# com_board.net
KiCad netlist of a schematic drawn in EAGLE
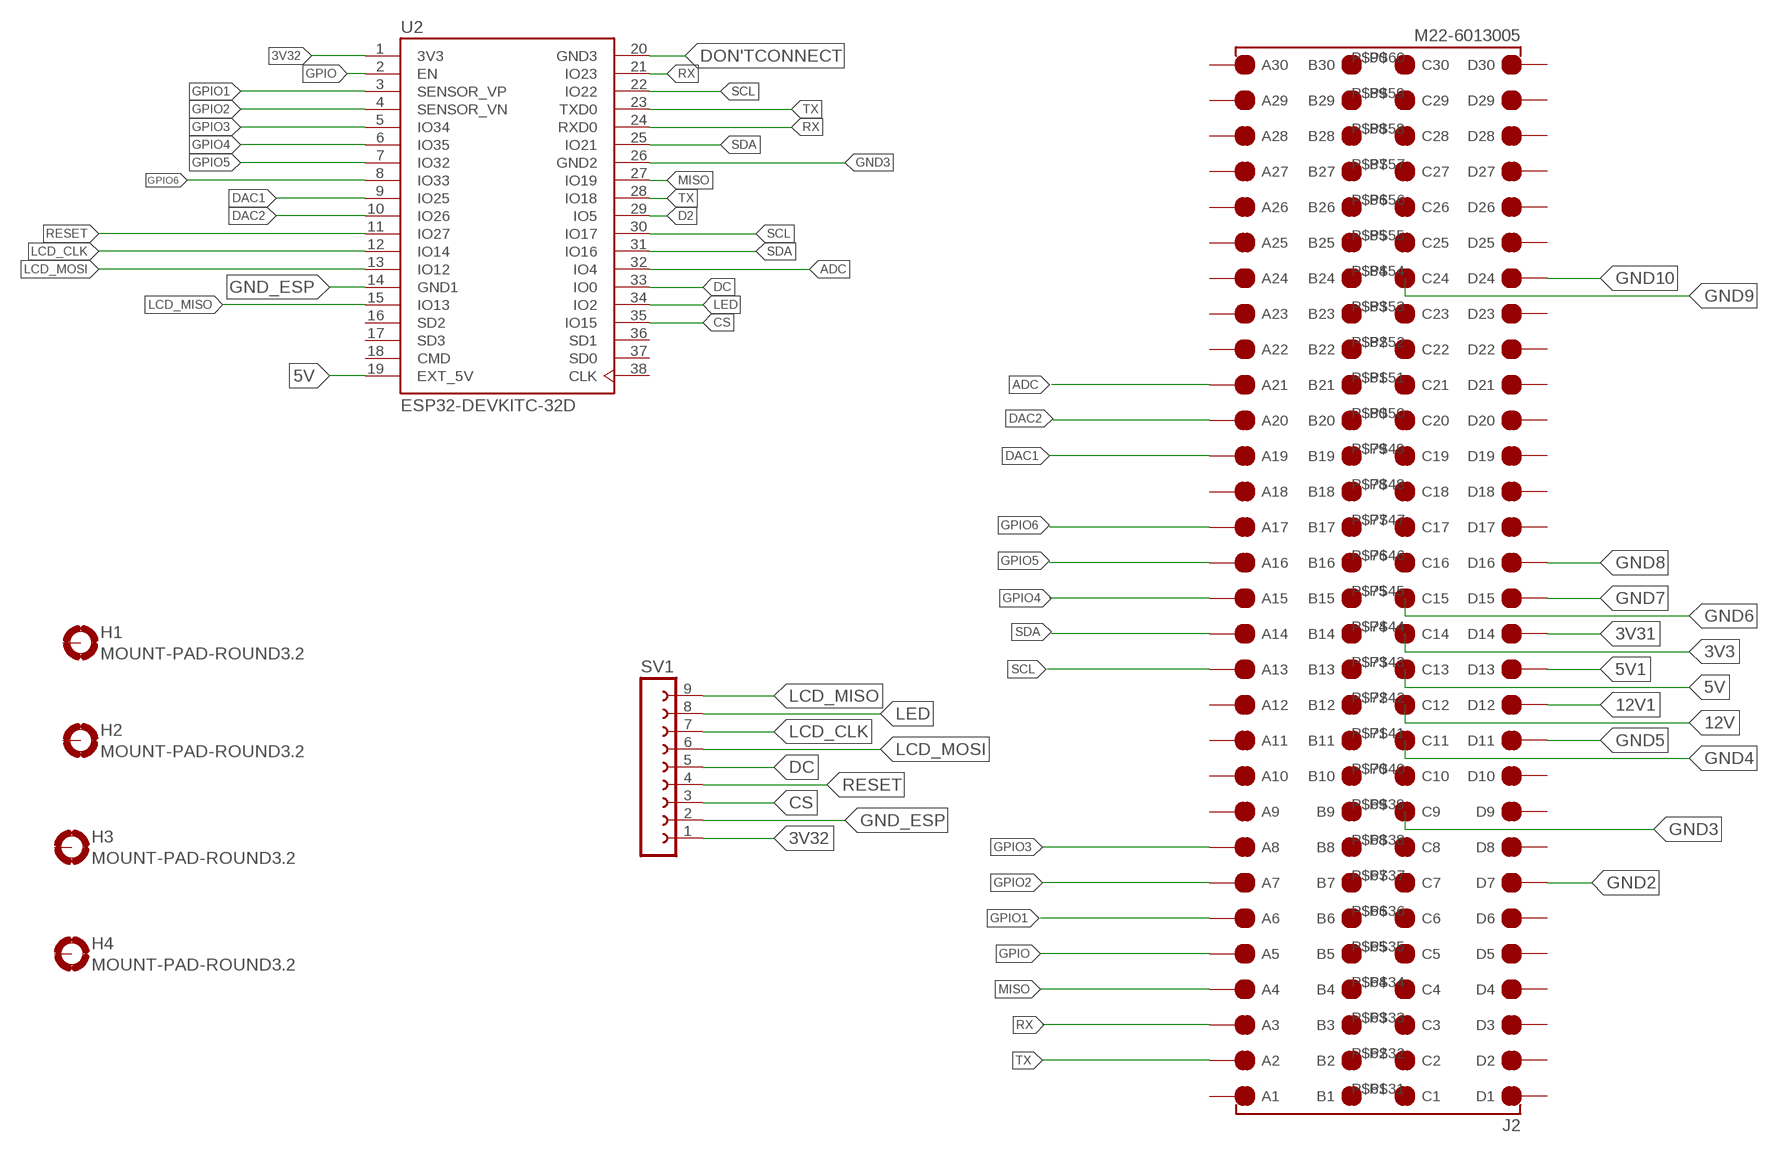
[diagram p0: schematic, sheet 1]

(export (version "E")
  (design (tool "Eeschema 10.0.6"))
  (components
    (comp (ref "H1")
      (value "MOUNT-PAD-ROUND3.2")
      (footprint "eagle-import:3,2-PAD")
      (libsource (lib "eagle-import") (part "MOUNT-PAD-ROUND3.2"))
    )
    (comp (ref "H2")
      (value "MOUNT-PAD-ROUND3.2")
      (footprint "eagle-import:3,2-PAD")
      (libsource (lib "eagle-import") (part "MOUNT-PAD-ROUND3.2"))
    )
    (comp (ref "H3")
      (value "MOUNT-PAD-ROUND3.2")
      (footprint "eagle-import:3,2-PAD")
      (libsource (lib "eagle-import") (part "MOUNT-PAD-ROUND3.2"))
    )
    (comp (ref "H4")
      (value "MOUNT-PAD-ROUND3.2")
      (footprint "eagle-import:3,2-PAD")
      (libsource (lib "eagle-import") (part "MOUNT-PAD-ROUND3.2"))
    )
    (comp (ref "J2")
      (value "M22-6013005")
      (footprint "eagle-import:RHDR120W55P200_4X30_6020X820X9")
      (libsource (lib "eagle-import") (part "M22-6013005"))
    )
    (comp (ref "SV1")
      (value "FE09-1")
      (footprint "eagle-import:FE09")
      (libsource (lib "eagle-import") (part "FE09-1"))
    )
    (comp (ref "U2")
      (value "ESP32-DEVKITC-32D")
      (footprint "eagle-import:MODULE_ESP32-DEVKITC-32D")
      (fields (field (name "MF") "Espressif Systems"))
      (libsource (lib "eagle-import") (part "ESP32-DEVKITC-32D"))
    )
  )
  (nets
    (net (code "1") (name "3V3") (class "Default")
      (node (ref "J2") (pin "P$44") (pinfunction "C14_P$44") (pintype "passive"))
    )
    (net (code "2") (name "3V31") (class "Default")
      (node (ref "J2") (pin "P$14") (pinfunction "D14_P$14") (pintype "passive"))
    )
    (net (code "3") (name "3V32") (class "Default")
      (node (ref "SV1") (pin "1") (pinfunction "1_1") (pintype "passive"))
      (node (ref "U2") (pin "1") (pinfunction "3V3_1") (pintype "power_in"))
    )
    (net (code "4") (name "5V") (class "Default")
      (node (ref "J2") (pin "P$43") (pinfunction "C13_P$43") (pintype "passive"))
      (node (ref "U2") (pin "19") (pinfunction "EXT_5V_19") (pintype "power_in"))
    )
    (net (code "5") (name "5V1") (class "Default")
      (node (ref "J2") (pin "P$13") (pinfunction "D13_P$13") (pintype "passive"))
    )
    (net (code "6") (name "12V") (class "Default")
      (node (ref "J2") (pin "P$42") (pinfunction "C12_P$42") (pintype "passive"))
    )
    (net (code "7") (name "12V1") (class "Default")
      (node (ref "J2") (pin "P$12") (pinfunction "D12_P$12") (pintype "passive"))
    )
    (net (code "8") (name "ADC") (class "Default")
      (node (ref "J2") (pin "P$111") (pinfunction "A21_P$111") (pintype "passive"))
      (node (ref "U2") (pin "32") (pinfunction "IO4_32") (pintype "bidirectional"))
    )
    (net (code "9") (name "CS") (class "Default")
      (node (ref "SV1") (pin "3") (pinfunction "3_3") (pintype "passive"))
      (node (ref "U2") (pin "35") (pinfunction "IO15_35") (pintype "bidirectional"))
    )
    (net (code "10") (name "D2") (class "Default")
      (node (ref "U2") (pin "29") (pinfunction "IO5_29") (pintype "bidirectional"))
    )
    (net (code "11") (name "DAC1") (class "Default")
      (node (ref "J2") (pin "P$109") (pinfunction "A19_P$109") (pintype "passive"))
      (node (ref "U2") (pin "9") (pinfunction "IO25_9") (pintype "bidirectional"))
    )
    (net (code "12") (name "DAC2") (class "Default")
      (node (ref "J2") (pin "P$110") (pinfunction "A20_P$110") (pintype "passive"))
      (node (ref "U2") (pin "10") (pinfunction "IO26_10") (pintype "bidirectional"))
    )
    (net (code "13") (name "DC") (class "Default")
      (node (ref "SV1") (pin "5") (pinfunction "5_5") (pintype "passive"))
      (node (ref "U2") (pin "33") (pinfunction "IO0_33") (pintype "bidirectional"))
    )
    (net (code "14") (name "DON'TCONNECT") (class "Default")
      (node (ref "U2") (pin "20") (pinfunction "GND3_20") (pintype "power_in"))
    )
    (net (code "15") (name "GND2") (class "Default")
      (node (ref "J2") (pin "P$7") (pinfunction "D7_P$7") (pintype "passive"))
    )
    (net (code "16") (name "GND3") (class "Default")
      (node (ref "J2") (pin "P$39") (pinfunction "C9_P$39") (pintype "passive"))
      (node (ref "U2") (pin "26") (pinfunction "GND2_26") (pintype "power_in"))
    )
    (net (code "17") (name "GND4") (class "Default")
      (node (ref "J2") (pin "P$41") (pinfunction "C11_P$41") (pintype "passive"))
    )
    (net (code "18") (name "GND5") (class "Default")
      (node (ref "J2") (pin "P$11") (pinfunction "D11_P$11") (pintype "passive"))
    )
    (net (code "19") (name "GND6") (class "Default")
      (node (ref "J2") (pin "P$45") (pinfunction "C15_P$45") (pintype "passive"))
    )
    (net (code "20") (name "GND7") (class "Default")
      (node (ref "J2") (pin "P$15") (pinfunction "D15_P$15") (pintype "passive"))
    )
    (net (code "21") (name "GND8") (class "Default")
      (node (ref "J2") (pin "P$16") (pinfunction "D16_P$16") (pintype "passive"))
    )
    (net (code "22") (name "GND9") (class "Default")
      (node (ref "J2") (pin "P$54") (pinfunction "C24_P$54") (pintype "passive"))
    )
    (net (code "23") (name "GND10") (class "Default")
      (node (ref "J2") (pin "P$24") (pinfunction "D24_P$24") (pintype "passive"))
    )
    (net (code "24") (name "GND_ESP") (class "Default")
      (node (ref "SV1") (pin "2") (pinfunction "2_2") (pintype "passive"))
      (node (ref "U2") (pin "14") (pinfunction "GND1_14") (pintype "power_in"))
    )
    (net (code "25") (name "GPIO") (class "Default")
      (node (ref "J2") (pin "P$95") (pinfunction "A5_P$95") (pintype "passive"))
      (node (ref "U2") (pin "2") (pinfunction "EN_2") (pintype "input"))
    )
    (net (code "26") (name "GPIO1") (class "Default")
      (node (ref "J2") (pin "P$96") (pinfunction "A6_P$96") (pintype "passive"))
      (node (ref "U2") (pin "3") (pinfunction "SENSOR_VP_3") (pintype "input"))
    )
    (net (code "27") (name "GPIO2") (class "Default")
      (node (ref "J2") (pin "P$97") (pinfunction "A7_P$97") (pintype "passive"))
      (node (ref "U2") (pin "4") (pinfunction "SENSOR_VN_4") (pintype "input"))
    )
    (net (code "28") (name "GPIO3") (class "Default")
      (node (ref "J2") (pin "P$98") (pinfunction "A8_P$98") (pintype "passive"))
      (node (ref "U2") (pin "5") (pinfunction "IO34_5") (pintype "bidirectional"))
    )
    (net (code "29") (name "GPIO4") (class "Default")
      (node (ref "J2") (pin "P$105") (pinfunction "A15_P$105") (pintype "passive"))
      (node (ref "U2") (pin "6") (pinfunction "IO35_6") (pintype "bidirectional"))
    )
    (net (code "30") (name "GPIO5") (class "Default")
      (node (ref "J2") (pin "P$106") (pinfunction "A16_P$106") (pintype "passive"))
      (node (ref "U2") (pin "7") (pinfunction "IO32_7") (pintype "bidirectional"))
    )
    (net (code "31") (name "GPIO6") (class "Default")
      (node (ref "J2") (pin "P$107") (pinfunction "A17_P$107") (pintype "passive"))
      (node (ref "U2") (pin "8") (pinfunction "IO33_8") (pintype "bidirectional"))
    )
    (net (code "32") (name "LCD_CLK") (class "Default")
      (node (ref "SV1") (pin "7") (pinfunction "7_7") (pintype "passive"))
      (node (ref "U2") (pin "12") (pinfunction "IO14_12") (pintype "bidirectional"))
    )
    (net (code "33") (name "LCD_MISO") (class "Default")
      (node (ref "SV1") (pin "9") (pinfunction "9_9") (pintype "passive"))
      (node (ref "U2") (pin "15") (pinfunction "IO13_15") (pintype "bidirectional"))
    )
    (net (code "34") (name "LCD_MOSI") (class "Default")
      (node (ref "SV1") (pin "6") (pinfunction "6_6") (pintype "passive"))
      (node (ref "U2") (pin "13") (pinfunction "IO12_13") (pintype "bidirectional"))
    )
    (net (code "35") (name "LED") (class "Default")
      (node (ref "SV1") (pin "8") (pinfunction "8_8") (pintype "passive"))
      (node (ref "U2") (pin "34") (pinfunction "IO2_34") (pintype "bidirectional"))
    )
    (net (code "36") (name "MISO") (class "Default")
      (node (ref "J2") (pin "P$94") (pinfunction "A4_P$94") (pintype "passive"))
      (node (ref "U2") (pin "27") (pinfunction "IO19_27") (pintype "bidirectional"))
    )
    (net (code "37") (name "RESET") (class "Default")
      (node (ref "SV1") (pin "4") (pinfunction "4_4") (pintype "passive"))
      (node (ref "U2") (pin "11") (pinfunction "IO27_11") (pintype "bidirectional"))
    )
    (net (code "38") (name "RX") (class "Default")
      (node (ref "J2") (pin "P$93") (pinfunction "A3_P$93") (pintype "passive"))
      (node (ref "U2") (pin "21") (pinfunction "IO23_21") (pintype "bidirectional"))
      (node (ref "U2") (pin "24") (pinfunction "RXD0_24") (pintype "input"))
    )
    (net (code "39") (name "SCL") (class "Default")
      (node (ref "J2") (pin "P$103") (pinfunction "A13_P$103") (pintype "passive"))
      (node (ref "U2") (pin "22") (pinfunction "IO22_22") (pintype "bidirectional"))
      (node (ref "U2") (pin "30") (pinfunction "IO17_30") (pintype "bidirectional"))
    )
    (net (code "40") (name "SDA") (class "Default")
      (node (ref "J2") (pin "P$104") (pinfunction "A14_P$104") (pintype "passive"))
      (node (ref "U2") (pin "25") (pinfunction "IO21_25") (pintype "bidirectional"))
      (node (ref "U2") (pin "31") (pinfunction "IO16_31") (pintype "bidirectional"))
    )
    (net (code "41") (name "TX") (class "Default")
      (node (ref "J2") (pin "P$92") (pinfunction "A2_P$92") (pintype "passive"))
      (node (ref "U2") (pin "23") (pinfunction "TXD0_23") (pintype "output"))
      (node (ref "U2") (pin "28") (pinfunction "IO18_28") (pintype "bidirectional"))
    )
    (net (code "42") (name "unconnected-(H1-MOUNT-PadB3,2)") (class "Default")
      (node (ref "H1") (pin "B3,2") (pinfunction "MOUNT_B3,2") (pintype "passive"))
    )
    (net (code "43") (name "unconnected-(H2-MOUNT-PadB3,2)") (class "Default")
      (node (ref "H2") (pin "B3,2") (pinfunction "MOUNT_B3,2") (pintype "passive"))
    )
    (net (code "44") (name "unconnected-(H3-MOUNT-PadB3,2)") (class "Default")
      (node (ref "H3") (pin "B3,2") (pinfunction "MOUNT_B3,2") (pintype "passive"))
    )
    (net (code "45") (name "unconnected-(H4-MOUNT-PadB3,2)") (class "Default")
      (node (ref "H4") (pin "B3,2") (pinfunction "MOUNT_B3,2") (pintype "passive"))
    )
    (net (code "46") (name "unconnected-(J2-A1-PadP$91)") (class "Default")
      (node (ref "J2") (pin "P$91") (pinfunction "A1_P$91") (pintype "passive"))
    )
    (net (code "47") (name "unconnected-(J2-A9-PadP$99)") (class "Default")
      (node (ref "J2") (pin "P$99") (pinfunction "A9_P$99") (pintype "passive"))
    )
    (net (code "48") (name "unconnected-(J2-A10-PadP$100)") (class "Default")
      (node (ref "J2") (pin "P$100") (pinfunction "A10_P$100") (pintype "passive"))
    )
    (net (code "49") (name "unconnected-(J2-A11-PadP$101)") (class "Default")
      (node (ref "J2") (pin "P$101") (pinfunction "A11_P$101") (pintype "passive"))
    )
    (net (code "50") (name "unconnected-(J2-A12-PadP$102)") (class "Default")
      (node (ref "J2") (pin "P$102") (pinfunction "A12_P$102") (pintype "passive"))
    )
    (net (code "51") (name "unconnected-(J2-A18-PadP$108)") (class "Default")
      (node (ref "J2") (pin "P$108") (pinfunction "A18_P$108") (pintype "passive"))
    )
    (net (code "52") (name "unconnected-(J2-A22-PadP$112)") (class "Default")
      (node (ref "J2") (pin "P$112") (pinfunction "A22_P$112") (pintype "passive"))
    )
    (net (code "53") (name "unconnected-(J2-A23-PadP$113)") (class "Default")
      (node (ref "J2") (pin "P$113") (pinfunction "A23_P$113") (pintype "passive"))
    )
    (net (code "54") (name "unconnected-(J2-A24-PadP$114)") (class "Default")
      (node (ref "J2") (pin "P$114") (pinfunction "A24_P$114") (pintype "passive"))
    )
    (net (code "55") (name "unconnected-(J2-A25-PadP$115)") (class "Default")
      (node (ref "J2") (pin "P$115") (pinfunction "A25_P$115") (pintype "passive"))
    )
    (net (code "56") (name "unconnected-(J2-A26-PadP$116)") (class "Default")
      (node (ref "J2") (pin "P$116") (pinfunction "A26_P$116") (pintype "passive"))
    )
    (net (code "57") (name "unconnected-(J2-A27-PadP$117)") (class "Default")
      (node (ref "J2") (pin "P$117") (pinfunction "A27_P$117") (pintype "passive"))
    )
    (net (code "58") (name "unconnected-(J2-A28-PadP$118)") (class "Default")
      (node (ref "J2") (pin "P$118") (pinfunction "A28_P$118") (pintype "passive"))
    )
    (net (code "59") (name "unconnected-(J2-A29-PadP$119)") (class "Default")
      (node (ref "J2") (pin "P$119") (pinfunction "A29_P$119") (pintype "passive"))
    )
    (net (code "60") (name "unconnected-(J2-A30-PadP$120)") (class "Default")
      (node (ref "J2") (pin "P$120") (pinfunction "A30_P$120") (pintype "passive"))
    )
    (net (code "61") (name "unconnected-(J2-B1-PadP$61)") (class "Default")
      (node (ref "J2") (pin "P$61") (pinfunction "B1_P$61") (pintype "passive"))
    )
    (net (code "62") (name "unconnected-(J2-B2-PadP$62)") (class "Default")
      (node (ref "J2") (pin "P$62") (pinfunction "B2_P$62") (pintype "passive"))
    )
    (net (code "63") (name "unconnected-(J2-B3-PadP$63)") (class "Default")
      (node (ref "J2") (pin "P$63") (pinfunction "B3_P$63") (pintype "passive"))
    )
    (net (code "64") (name "unconnected-(J2-B4-PadP$64)") (class "Default")
      (node (ref "J2") (pin "P$64") (pinfunction "B4_P$64") (pintype "passive"))
    )
    (net (code "65") (name "unconnected-(J2-B5-PadP$65)") (class "Default")
      (node (ref "J2") (pin "P$65") (pinfunction "B5_P$65") (pintype "passive"))
    )
    (net (code "66") (name "unconnected-(J2-B6-PadP$66)") (class "Default")
      (node (ref "J2") (pin "P$66") (pinfunction "B6_P$66") (pintype "passive"))
    )
    (net (code "67") (name "unconnected-(J2-B7-PadP$67)") (class "Default")
      (node (ref "J2") (pin "P$67") (pinfunction "B7_P$67") (pintype "passive"))
    )
    (net (code "68") (name "unconnected-(J2-B8-PadP$68)") (class "Default")
      (node (ref "J2") (pin "P$68") (pinfunction "B8_P$68") (pintype "passive"))
    )
    (net (code "69") (name "unconnected-(J2-B9-PadP$69)") (class "Default")
      (node (ref "J2") (pin "P$69") (pinfunction "B9_P$69") (pintype "passive"))
    )
    (net (code "70") (name "unconnected-(J2-B10-PadP$70)") (class "Default")
      (node (ref "J2") (pin "P$70") (pinfunction "B10_P$70") (pintype "passive"))
    )
    (net (code "71") (name "unconnected-(J2-B11-PadP$71)") (class "Default")
      (node (ref "J2") (pin "P$71") (pinfunction "B11_P$71") (pintype "passive"))
    )
    (net (code "72") (name "unconnected-(J2-B12-PadP$72)") (class "Default")
      (node (ref "J2") (pin "P$72") (pinfunction "B12_P$72") (pintype "passive"))
    )
    (net (code "73") (name "unconnected-(J2-B13-PadP$73)") (class "Default")
      (node (ref "J2") (pin "P$73") (pinfunction "B13_P$73") (pintype "passive"))
    )
    (net (code "74") (name "unconnected-(J2-B14-PadP$74)") (class "Default")
      (node (ref "J2") (pin "P$74") (pinfunction "B14_P$74") (pintype "passive"))
    )
    (net (code "75") (name "unconnected-(J2-B15-PadP$75)") (class "Default")
      (node (ref "J2") (pin "P$75") (pinfunction "B15_P$75") (pintype "passive"))
    )
    (net (code "76") (name "unconnected-(J2-B16-PadP$76)") (class "Default")
      (node (ref "J2") (pin "P$76") (pinfunction "B16_P$76") (pintype "passive"))
    )
    (net (code "77") (name "unconnected-(J2-B17-PadP$77)") (class "Default")
      (node (ref "J2") (pin "P$77") (pinfunction "B17_P$77") (pintype "passive"))
    )
    (net (code "78") (name "unconnected-(J2-B18-PadP$78)") (class "Default")
      (node (ref "J2") (pin "P$78") (pinfunction "B18_P$78") (pintype "passive"))
    )
    (net (code "79") (name "unconnected-(J2-B19-PadP$79)") (class "Default")
      (node (ref "J2") (pin "P$79") (pinfunction "B19_P$79") (pintype "passive"))
    )
    (net (code "80") (name "unconnected-(J2-B20-PadP$80)") (class "Default")
      (node (ref "J2") (pin "P$80") (pinfunction "B20_P$80") (pintype "passive"))
    )
    (net (code "81") (name "unconnected-(J2-B21-PadP$81)") (class "Default")
      (node (ref "J2") (pin "P$81") (pinfunction "B21_P$81") (pintype "passive"))
    )
    (net (code "82") (name "unconnected-(J2-B22-PadP$82)") (class "Default")
      (node (ref "J2") (pin "P$82") (pinfunction "B22_P$82") (pintype "passive"))
    )
    (net (code "83") (name "unconnected-(J2-B23-PadP$83)") (class "Default")
      (node (ref "J2") (pin "P$83") (pinfunction "B23_P$83") (pintype "passive"))
    )
    (net (code "84") (name "unconnected-(J2-B24-PadP$84)") (class "Default")
      (node (ref "J2") (pin "P$84") (pinfunction "B24_P$84") (pintype "passive"))
    )
    (net (code "85") (name "unconnected-(J2-B25-PadP$85)") (class "Default")
      (node (ref "J2") (pin "P$85") (pinfunction "B25_P$85") (pintype "passive"))
    )
    (net (code "86") (name "unconnected-(J2-B26-PadP$86)") (class "Default")
      (node (ref "J2") (pin "P$86") (pinfunction "B26_P$86") (pintype "passive"))
    )
    (net (code "87") (name "unconnected-(J2-B27-PadP$87)") (class "Default")
      (node (ref "J2") (pin "P$87") (pinfunction "B27_P$87") (pintype "passive"))
    )
    (net (code "88") (name "unconnected-(J2-B28-PadP$88)") (class "Default")
      (node (ref "J2") (pin "P$88") (pinfunction "B28_P$88") (pintype "passive"))
    )
    (net (code "89") (name "unconnected-(J2-B29-PadP$89)") (class "Default")
      (node (ref "J2") (pin "P$89") (pinfunction "B29_P$89") (pintype "passive"))
    )
    (net (code "90") (name "unconnected-(J2-B30-PadP$90)") (class "Default")
      (node (ref "J2") (pin "P$90") (pinfunction "B30_P$90") (pintype "passive"))
    )
    (net (code "91") (name "unconnected-(J2-C1-PadP$31)") (class "Default")
      (node (ref "J2") (pin "P$31") (pinfunction "C1_P$31") (pintype "passive"))
    )
    (net (code "92") (name "unconnected-(J2-C2-PadP$32)") (class "Default")
      (node (ref "J2") (pin "P$32") (pinfunction "C2_P$32") (pintype "passive"))
    )
    (net (code "93") (name "unconnected-(J2-C3-PadP$33)") (class "Default")
      (node (ref "J2") (pin "P$33") (pinfunction "C3_P$33") (pintype "passive"))
    )
    (net (code "94") (name "unconnected-(J2-C4-PadP$34)") (class "Default")
      (node (ref "J2") (pin "P$34") (pinfunction "C4_P$34") (pintype "passive"))
    )
    (net (code "95") (name "unconnected-(J2-C5-PadP$35)") (class "Default")
      (node (ref "J2") (pin "P$35") (pinfunction "C5_P$35") (pintype "passive"))
    )
    (net (code "96") (name "unconnected-(J2-C6-PadP$36)") (class "Default")
      (node (ref "J2") (pin "P$36") (pinfunction "C6_P$36") (pintype "passive"))
    )
    (net (code "97") (name "unconnected-(J2-C7-PadP$37)") (class "Default")
      (node (ref "J2") (pin "P$37") (pinfunction "C7_P$37") (pintype "passive"))
    )
    (net (code "98") (name "unconnected-(J2-C8-PadP$38)") (class "Default")
      (node (ref "J2") (pin "P$38") (pinfunction "C8_P$38") (pintype "passive"))
    )
    (net (code "99") (name "unconnected-(J2-C10-PadP$40)") (class "Default")
      (node (ref "J2") (pin "P$40") (pinfunction "C10_P$40") (pintype "passive"))
    )
    (net (code "100") (name "unconnected-(J2-C16-PadP$46)") (class "Default")
      (node (ref "J2") (pin "P$46") (pinfunction "C16_P$46") (pintype "passive"))
    )
    (net (code "101") (name "unconnected-(J2-C17-PadP$47)") (class "Default")
      (node (ref "J2") (pin "P$47") (pinfunction "C17_P$47") (pintype "passive"))
    )
    (net (code "102") (name "unconnected-(J2-C18-PadP$48)") (class "Default")
      (node (ref "J2") (pin "P$48") (pinfunction "C18_P$48") (pintype "passive"))
    )
    (net (code "103") (name "unconnected-(J2-C19-PadP$49)") (class "Default")
      (node (ref "J2") (pin "P$49") (pinfunction "C19_P$49") (pintype "passive"))
    )
    (net (code "104") (name "unconnected-(J2-C20-PadP$50)") (class "Default")
      (node (ref "J2") (pin "P$50") (pinfunction "C20_P$50") (pintype "passive"))
    )
    (net (code "105") (name "unconnected-(J2-C21-PadP$51)") (class "Default")
      (node (ref "J2") (pin "P$51") (pinfunction "C21_P$51") (pintype "passive"))
    )
    (net (code "106") (name "unconnected-(J2-C22-PadP$52)") (class "Default")
      (node (ref "J2") (pin "P$52") (pinfunction "C22_P$52") (pintype "passive"))
    )
    (net (code "107") (name "unconnected-(J2-C23-PadP$53)") (class "Default")
      (node (ref "J2") (pin "P$53") (pinfunction "C23_P$53") (pintype "passive"))
    )
    (net (code "108") (name "unconnected-(J2-C25-PadP$55)") (class "Default")
      (node (ref "J2") (pin "P$55") (pinfunction "C25_P$55") (pintype "passive"))
    )
    (net (code "109") (name "unconnected-(J2-C26-PadP$56)") (class "Default")
      (node (ref "J2") (pin "P$56") (pinfunction "C26_P$56") (pintype "passive"))
    )
    (net (code "110") (name "unconnected-(J2-C27-PadP$57)") (class "Default")
      (node (ref "J2") (pin "P$57") (pinfunction "C27_P$57") (pintype "passive"))
    )
    (net (code "111") (name "unconnected-(J2-C28-PadP$58)") (class "Default")
      (node (ref "J2") (pin "P$58") (pinfunction "C28_P$58") (pintype "passive"))
    )
    (net (code "112") (name "unconnected-(J2-C29-PadP$59)") (class "Default")
      (node (ref "J2") (pin "P$59") (pinfunction "C29_P$59") (pintype "passive"))
    )
    (net (code "113") (name "unconnected-(J2-C30-PadP$60)") (class "Default")
      (node (ref "J2") (pin "P$60") (pinfunction "C30_P$60") (pintype "passive"))
    )
    (net (code "114") (name "unconnected-(J2-D1-PadP$1)") (class "Default")
      (node (ref "J2") (pin "P$1") (pinfunction "D1_P$1") (pintype "passive"))
    )
    (net (code "115") (name "unconnected-(J2-D2-PadP$2)") (class "Default")
      (node (ref "J2") (pin "P$2") (pinfunction "D2_P$2") (pintype "passive"))
    )
    (net (code "116") (name "unconnected-(J2-D3-PadP$3)") (class "Default")
      (node (ref "J2") (pin "P$3") (pinfunction "D3_P$3") (pintype "passive"))
    )
    (net (code "117") (name "unconnected-(J2-D4-PadP$4)") (class "Default")
      (node (ref "J2") (pin "P$4") (pinfunction "D4_P$4") (pintype "passive"))
    )
    (net (code "118") (name "unconnected-(J2-D5-PadP$5)") (class "Default")
      (node (ref "J2") (pin "P$5") (pinfunction "D5_P$5") (pintype "passive"))
    )
    (net (code "119") (name "unconnected-(J2-D6-PadP$6)") (class "Default")
      (node (ref "J2") (pin "P$6") (pinfunction "D6_P$6") (pintype "passive"))
    )
    (net (code "120") (name "unconnected-(J2-D8-PadP$8)") (class "Default")
      (node (ref "J2") (pin "P$8") (pinfunction "D8_P$8") (pintype "passive"))
    )
    (net (code "121") (name "unconnected-(J2-D9-PadP$9)") (class "Default")
      (node (ref "J2") (pin "P$9") (pinfunction "D9_P$9") (pintype "passive"))
    )
    (net (code "122") (name "unconnected-(J2-D10-PadP$10)") (class "Default")
      (node (ref "J2") (pin "P$10") (pinfunction "D10_P$10") (pintype "passive"))
    )
    (net (code "123") (name "unconnected-(J2-D17-PadP$17)") (class "Default")
      (node (ref "J2") (pin "P$17") (pinfunction "D17_P$17") (pintype "passive"))
    )
    (net (code "124") (name "unconnected-(J2-D18-PadP$18)") (class "Default")
      (node (ref "J2") (pin "P$18") (pinfunction "D18_P$18") (pintype "passive"))
    )
    (net (code "125") (name "unconnected-(J2-D19-PadP$19)") (class "Default")
      (node (ref "J2") (pin "P$19") (pinfunction "D19_P$19") (pintype "passive"))
    )
    (net (code "126") (name "unconnected-(J2-D20-PadP$20)") (class "Default")
      (node (ref "J2") (pin "P$20") (pinfunction "D20_P$20") (pintype "passive"))
    )
    (net (code "127") (name "unconnected-(J2-D21-PadP$21)") (class "Default")
      (node (ref "J2") (pin "P$21") (pinfunction "D21_P$21") (pintype "passive"))
    )
    (net (code "128") (name "unconnected-(J2-D22-PadP$22)") (class "Default")
      (node (ref "J2") (pin "P$22") (pinfunction "D22_P$22") (pintype "passive"))
    )
    (net (code "129") (name "unconnected-(J2-D23-PadP$23)") (class "Default")
      (node (ref "J2") (pin "P$23") (pinfunction "D23_P$23") (pintype "passive"))
    )
    (net (code "130") (name "unconnected-(J2-D25-PadP$25)") (class "Default")
      (node (ref "J2") (pin "P$25") (pinfunction "D25_P$25") (pintype "passive"))
    )
    (net (code "131") (name "unconnected-(J2-D26-PadP$26)") (class "Default")
      (node (ref "J2") (pin "P$26") (pinfunction "D26_P$26") (pintype "passive"))
    )
    (net (code "132") (name "unconnected-(J2-D27-PadP$27)") (class "Default")
      (node (ref "J2") (pin "P$27") (pinfunction "D27_P$27") (pintype "passive"))
    )
    (net (code "133") (name "unconnected-(J2-D28-PadP$28)") (class "Default")
      (node (ref "J2") (pin "P$28") (pinfunction "D28_P$28") (pintype "passive"))
    )
    (net (code "134") (name "unconnected-(J2-D29-PadP$29)") (class "Default")
      (node (ref "J2") (pin "P$29") (pinfunction "D29_P$29") (pintype "passive"))
    )
    (net (code "135") (name "unconnected-(J2-D30-PadP$30)") (class "Default")
      (node (ref "J2") (pin "P$30") (pinfunction "D30_P$30") (pintype "passive"))
    )
    (net (code "136") (name "unconnected-(U2-CLK-Pad38)") (class "Default")
      (node (ref "U2") (pin "38") (pinfunction "CLK_38") (pintype "input"))
    )
    (net (code "137") (name "unconnected-(U2-CMD-Pad18)") (class "Default")
      (node (ref "U2") (pin "18") (pinfunction "CMD_18") (pintype "bidirectional"))
    )
    (net (code "138") (name "unconnected-(U2-SD0-Pad37)") (class "Default")
      (node (ref "U2") (pin "37") (pinfunction "SD0_37") (pintype "bidirectional"))
    )
    (net (code "139") (name "unconnected-(U2-SD1-Pad36)") (class "Default")
      (node (ref "U2") (pin "36") (pinfunction "SD1_36") (pintype "bidirectional"))
    )
    (net (code "140") (name "unconnected-(U2-SD2-Pad16)") (class "Default")
      (node (ref "U2") (pin "16") (pinfunction "SD2_16") (pintype "bidirectional"))
    )
    (net (code "141") (name "unconnected-(U2-SD3-Pad17)") (class "Default")
      (node (ref "U2") (pin "17") (pinfunction "SD3_17") (pintype "bidirectional"))
    )
  )
)
